# Sedna_Monitor_Board.net
KiCad netlist of a schematic drawn in EAGLE
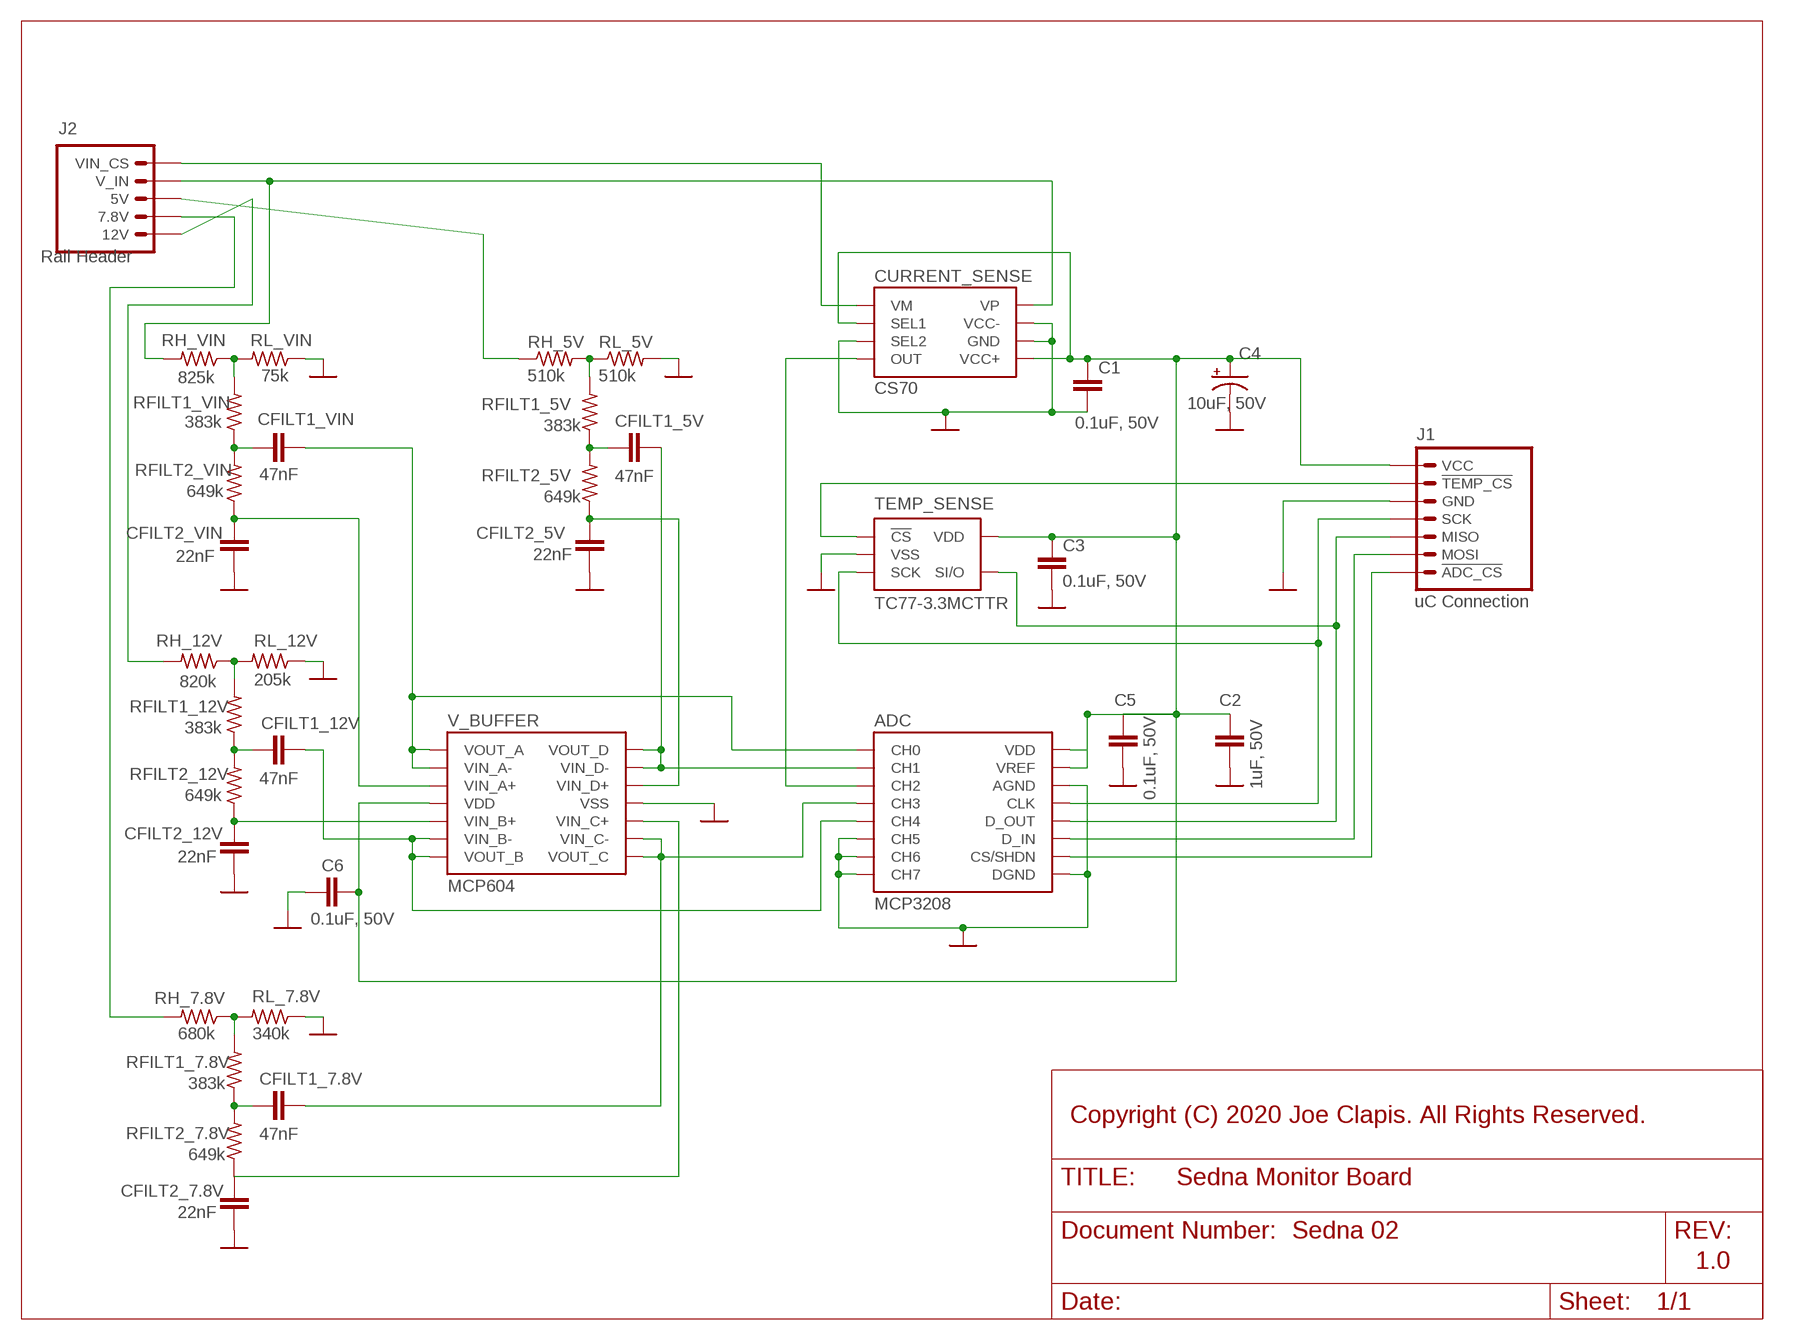
[diagram p0: schematic, sheet 1]

(export (version "E")
  (design (tool "Eeschema 10.0.6"))
  (components
    (comp (ref "ADC")
      (value "MCP3208")
      (footprint "eagle-import:MICROCHIP_SOIC-16_SL")
      (libsource (lib "eagle-import") (part "MCP3208"))
    )
    (comp (ref "C1")
      (value "0.1uF, 50V")
      (footprint "eagle-import:C0805")
      (libsource (lib "eagle-import") (part "C-EUC0805"))
    )
    (comp (ref "C2")
      (value "1uF, 50V")
      (footprint "eagle-import:C0805")
      (libsource (lib "eagle-import") (part "C-EUC0805"))
    )
    (comp (ref "C3")
      (value "0.1uF, 50V")
      (footprint "eagle-import:C0805")
      (libsource (lib "eagle-import") (part "C-EUC0805"))
    )
    (comp (ref "C4")
      (value "10uF, 50V")
      (footprint "eagle-import:PANASONIC-SMD-CAP-SV-D")
      (libsource (lib "eagle-import") (part "PANASONIC-CAP-SV"))
    )
    (comp (ref "C5")
      (value "0.1uF, 50V")
      (footprint "eagle-import:C0805")
      (libsource (lib "eagle-import") (part "C-EUC0805"))
    )
    (comp (ref "C6")
      (value "0.1uF, 50V")
      (footprint "eagle-import:C0805")
      (libsource (lib "eagle-import") (part "C-EUC0805"))
    )
    (comp (ref "CFILT1_5V")
      (value "47nF")
      (footprint "eagle-import:C0805")
      (libsource (lib "eagle-import") (part "C-EUC0805"))
    )
    (comp (ref "CFILT1_7.8V")
      (value "47nF")
      (footprint "eagle-import:C0805")
      (libsource (lib "eagle-import") (part "C-EUC0805"))
    )
    (comp (ref "CFILT1_12V")
      (value "47nF")
      (footprint "eagle-import:C0805")
      (libsource (lib "eagle-import") (part "C-EUC0805"))
    )
    (comp (ref "CFILT1_VIN")
      (value "47nF")
      (footprint "eagle-import:C0805")
      (libsource (lib "eagle-import") (part "C-EUC0805"))
    )
    (comp (ref "CFILT2_5V")
      (value "22nF")
      (footprint "eagle-import:C0805")
      (libsource (lib "eagle-import") (part "C-EUC0805"))
    )
    (comp (ref "CFILT2_7.8V")
      (value "22nF")
      (footprint "eagle-import:C0805")
      (libsource (lib "eagle-import") (part "C-EUC0805"))
    )
    (comp (ref "CFILT2_12V")
      (value "22nF")
      (footprint "eagle-import:C0805")
      (libsource (lib "eagle-import") (part "C-EUC0805"))
    )
    (comp (ref "CFILT2_VIN")
      (value "22nF")
      (footprint "eagle-import:C0805")
      (libsource (lib "eagle-import") (part "C-EUC0805"))
    )
    (comp (ref "CURRENT_SENSE")
      (value "CS70")
      (footprint "eagle-import:TSSOP8")
      (libsource (lib "eagle-import") (part "CS70"))
    )
    (comp (ref "J1")
      (value "uC Connection")
      (footprint "eagle-import:1X07")
      (libsource (lib "eagle-import") (part "UC_MONITOR_HEADER"))
    )
    (comp (ref "J2")
      (value "Rail Header")
      (footprint "eagle-import:1X05")
      (libsource (lib "eagle-import") (part "RAIL_HEADER"))
    )
    (comp (ref "RFILT1_5V")
      (value "383k")
      (footprint "eagle-import:R0805")
      (libsource (lib "eagle-import") (part "R-US_R0805"))
    )
    (comp (ref "RFILT1_7.8V")
      (value "383k")
      (footprint "eagle-import:R0805")
      (libsource (lib "eagle-import") (part "R-US_R0805"))
    )
    (comp (ref "RFILT1_12V")
      (value "383k")
      (footprint "eagle-import:R0805")
      (libsource (lib "eagle-import") (part "R-US_R0805"))
    )
    (comp (ref "RFILT1_VIN")
      (value "383k")
      (footprint "eagle-import:R0805")
      (libsource (lib "eagle-import") (part "R-US_R0805"))
    )
    (comp (ref "RFILT2_5V")
      (value "649k")
      (footprint "eagle-import:R0805")
      (libsource (lib "eagle-import") (part "R-US_R0805"))
    )
    (comp (ref "RFILT2_7.8V")
      (value "649k")
      (footprint "eagle-import:R0805")
      (libsource (lib "eagle-import") (part "R-US_R0805"))
    )
    (comp (ref "RFILT2_12V")
      (value "649k")
      (footprint "eagle-import:R0805")
      (libsource (lib "eagle-import") (part "R-US_R0805"))
    )
    (comp (ref "RFILT2_VIN")
      (value "649k")
      (footprint "eagle-import:R0805")
      (libsource (lib "eagle-import") (part "R-US_R0805"))
    )
    (comp (ref "RH_5V")
      (value "510k")
      (footprint "eagle-import:R0805")
      (libsource (lib "eagle-import") (part "R-US_R0805"))
    )
    (comp (ref "RH_7.8V")
      (value "680k")
      (footprint "eagle-import:R0805")
      (libsource (lib "eagle-import") (part "R-US_R0805"))
    )
    (comp (ref "RH_12V")
      (value "820k")
      (footprint "eagle-import:R0805")
      (libsource (lib "eagle-import") (part "R-US_R0805"))
    )
    (comp (ref "RH_VIN")
      (value "825k")
      (footprint "eagle-import:R0805")
      (libsource (lib "eagle-import") (part "R-US_R0805"))
    )
    (comp (ref "RL_5V")
      (value "510k")
      (footprint "eagle-import:R0805")
      (libsource (lib "eagle-import") (part "R-US_R0805"))
    )
    (comp (ref "RL_7.8V")
      (value "340k")
      (footprint "eagle-import:R0805")
      (libsource (lib "eagle-import") (part "R-US_R0805"))
    )
    (comp (ref "RL_12V")
      (value "205k")
      (footprint "eagle-import:R0805")
      (libsource (lib "eagle-import") (part "R-US_R0805"))
    )
    (comp (ref "RL_VIN")
      (value "75k")
      (footprint "eagle-import:R0805")
      (libsource (lib "eagle-import") (part "R-US_R0805"))
    )
    (comp (ref "TEMP_SENSE")
      (value "TC77-3.3MCTTR")
      (footprint "eagle-import:MICROCHIP_SOT-23_5_OT")
      (libsource (lib "eagle-import") (part "TC77MCT"))
    )
    (comp (ref "V_BUFFER")
      (value "MCP604")
      (footprint "eagle-import:MICROCHIP_TSSOP-14_ST")
      (libsource (lib "eagle-import") (part "MCP604ST"))
    )
  )
  (nets
    (net (code "1") (name "GND") (class "Default")
      (node (ref "ADC") (pin "14") (pinfunction "AGND_14") (pintype "power_in"))
      (node (ref "ADC") (pin "6") (pinfunction "CH5_6") (pintype "input"))
      (node (ref "ADC") (pin "7") (pinfunction "CH6_7") (pintype "input"))
      (node (ref "ADC") (pin "8") (pinfunction "CH7_8") (pintype "input"))
      (node (ref "ADC") (pin "9") (pinfunction "DGND_9") (pintype "power_in"))
      (node (ref "C1") (pin "2") (pinfunction "2_2") (pintype "passive"))
      (node (ref "C2") (pin "2") (pinfunction "2_2") (pintype "passive"))
      (node (ref "C3") (pin "2") (pinfunction "2_2") (pintype "passive"))
      (node (ref "C4") (pin "GND") (pinfunction "-_GND") (pintype "passive"))
      (node (ref "C5") (pin "2") (pinfunction "2_2") (pintype "passive"))
      (node (ref "C6") (pin "2") (pinfunction "2_2") (pintype "passive"))
      (node (ref "CFILT2_12V") (pin "1") (pinfunction "1_1") (pintype "passive"))
      (node (ref "CFILT2_5V") (pin "1") (pinfunction "1_1") (pintype "passive"))
      (node (ref "CFILT2_7.8V") (pin "1") (pinfunction "1_1") (pintype "passive"))
      (node (ref "CFILT2_VIN") (pin "1") (pinfunction "1_1") (pintype "passive"))
      (node (ref "CURRENT_SENSE") (pin "3") (pinfunction "SEL2_3") (pintype "input"))
      (node (ref "CURRENT_SENSE") (pin "6") (pinfunction "GND_6") (pintype "power_in"))
      (node (ref "CURRENT_SENSE") (pin "7") (pinfunction "VCC-_7") (pintype "power_in"))
      (node (ref "J1") (pin "3") (pinfunction "GND_3") (pintype "output"))
      (node (ref "RL_12V") (pin "1") (pinfunction "1_1") (pintype "passive"))
      (node (ref "RL_5V") (pin "2") (pinfunction "2_2") (pintype "passive"))
      (node (ref "RL_7.8V") (pin "1") (pinfunction "1_1") (pintype "passive"))
      (node (ref "RL_VIN") (pin "1") (pinfunction "1_1") (pintype "passive"))
      (node (ref "TEMP_SENSE") (pin "2") (pinfunction "VSS_2") (pintype "power_in"))
      (node (ref "V_BUFFER") (pin "11") (pinfunction "VSS_11") (pintype "power_in"))
    )
    (net (code "2") (name "Net-(ADC-CH0)") (class "Default")
      (node (ref "ADC") (pin "1") (pinfunction "CH0_1") (pintype "input"))
      (node (ref "CFILT1_VIN") (pin "2") (pinfunction "2_2") (pintype "passive"))
      (node (ref "V_BUFFER") (pin "1") (pinfunction "VOUT_A_1") (pintype "output"))
      (node (ref "V_BUFFER") (pin "2") (pinfunction "VIN_A-_2") (pintype "input"))
    )
    (net (code "3") (name "Net-(ADC-CH1)") (class "Default")
      (node (ref "ADC") (pin "2") (pinfunction "CH1_2") (pintype "input"))
      (node (ref "CFILT1_5V") (pin "1") (pinfunction "1_1") (pintype "passive"))
      (node (ref "V_BUFFER") (pin "13") (pinfunction "VIN_D-_13") (pintype "input"))
      (node (ref "V_BUFFER") (pin "14") (pinfunction "VOUT_D_14") (pintype "output"))
    )
    (net (code "4") (name "Net-(ADC-CH2)") (class "Default")
      (node (ref "ADC") (pin "3") (pinfunction "CH2_3") (pintype "input"))
      (node (ref "CURRENT_SENSE") (pin "4") (pinfunction "OUT_4") (pintype "output"))
    )
    (net (code "5") (name "Net-(ADC-CH3)") (class "Default")
      (node (ref "ADC") (pin "4") (pinfunction "CH3_4") (pintype "input"))
      (node (ref "CFILT1_7.8V") (pin "1") (pinfunction "1_1") (pintype "passive"))
      (node (ref "V_BUFFER") (pin "8") (pinfunction "VOUT_C_8") (pintype "output"))
      (node (ref "V_BUFFER") (pin "9") (pinfunction "VIN_C-_9") (pintype "input"))
    )
    (net (code "6") (name "Net-(ADC-CH4)") (class "Default")
      (node (ref "ADC") (pin "5") (pinfunction "CH4_5") (pintype "input"))
      (node (ref "CFILT1_12V") (pin "2") (pinfunction "2_2") (pintype "passive"))
      (node (ref "V_BUFFER") (pin "6") (pinfunction "VIN_B-_6") (pintype "input"))
      (node (ref "V_BUFFER") (pin "7") (pinfunction "VOUT_B_7") (pintype "output"))
    )
    (net (code "7") (name "Net-(ADC-CLK)") (class "Default")
      (node (ref "ADC") (pin "13") (pinfunction "CLK_13") (pintype "input"))
      (node (ref "J1") (pin "4") (pinfunction "SCK_4") (pintype "output"))
      (node (ref "TEMP_SENSE") (pin "3") (pinfunction "SCK_3") (pintype "input"))
    )
    (net (code "8") (name "Net-(ADC-CS{slash}SHDN)") (class "Default")
      (node (ref "ADC") (pin "10") (pinfunction "CS/SHDN_10") (pintype "input"))
      (node (ref "J1") (pin "7") (pinfunction "~{ADC_CS}_7") (pintype "power_in"))
    )
    (net (code "9") (name "Net-(ADC-D_IN)") (class "Default")
      (node (ref "ADC") (pin "11") (pinfunction "D_IN_11") (pintype "input"))
      (node (ref "J1") (pin "6") (pinfunction "MOSI_6") (pintype "output"))
    )
    (net (code "10") (name "Net-(ADC-D_OUT)") (class "Default")
      (node (ref "ADC") (pin "12") (pinfunction "D_OUT_12") (pintype "output"))
      (node (ref "J1") (pin "5") (pinfunction "MISO_5") (pintype "input"))
      (node (ref "TEMP_SENSE") (pin "4") (pinfunction "SI/O_4") (pintype "output"))
    )
    (net (code "11") (name "Net-(ADC-VDD)") (class "Default")
      (node (ref "ADC") (pin "15") (pinfunction "VREF_15") (pintype "input"))
      (node (ref "ADC") (pin "16") (pinfunction "VDD_16") (pintype "power_in"))
      (node (ref "C1") (pin "1") (pinfunction "1_1") (pintype "passive"))
      (node (ref "C2") (pin "1") (pinfunction "1_1") (pintype "passive"))
      (node (ref "C3") (pin "1") (pinfunction "1_1") (pintype "passive"))
      (node (ref "C4") (pin "VDD") (pinfunction "+_VDD") (pintype "passive"))
      (node (ref "C5") (pin "1") (pinfunction "1_1") (pintype "passive"))
      (node (ref "C6") (pin "1") (pinfunction "1_1") (pintype "passive"))
      (node (ref "CURRENT_SENSE") (pin "2") (pinfunction "SEL1_2") (pintype "input"))
      (node (ref "CURRENT_SENSE") (pin "5") (pinfunction "VCC+_5") (pintype "power_in"))
      (node (ref "J1") (pin "1") (pinfunction "VCC_1") (pintype "power_in"))
      (node (ref "TEMP_SENSE") (pin "5") (pinfunction "VDD_5") (pintype "power_in"))
      (node (ref "V_BUFFER") (pin "4") (pinfunction "VDD_4") (pintype "power_in"))
    )
    (net (code "12") (name "Net-(CFILT1_5V-Pad2)") (class "Default")
      (node (ref "CFILT1_5V") (pin "2") (pinfunction "2_2") (pintype "passive"))
      (node (ref "RFILT1_5V") (pin "1") (pinfunction "1_1") (pintype "passive"))
      (node (ref "RFILT2_5V") (pin "2") (pinfunction "2_2") (pintype "passive"))
    )
    (net (code "13") (name "Net-(CFILT1_7.8V-Pad2)") (class "Default")
      (node (ref "CFILT1_7.8V") (pin "2") (pinfunction "2_2") (pintype "passive"))
      (node (ref "RFILT1_7.8V") (pin "1") (pinfunction "1_1") (pintype "passive"))
      (node (ref "RFILT2_7.8V") (pin "2") (pinfunction "2_2") (pintype "passive"))
    )
    (net (code "14") (name "Net-(CFILT1_12V-Pad1)") (class "Default")
      (node (ref "CFILT1_12V") (pin "1") (pinfunction "1_1") (pintype "passive"))
      (node (ref "RFILT1_12V") (pin "1") (pinfunction "1_1") (pintype "passive"))
      (node (ref "RFILT2_12V") (pin "2") (pinfunction "2_2") (pintype "passive"))
    )
    (net (code "15") (name "Net-(CFILT1_VIN-Pad1)") (class "Default")
      (node (ref "CFILT1_VIN") (pin "1") (pinfunction "1_1") (pintype "passive"))
      (node (ref "RFILT1_VIN") (pin "1") (pinfunction "1_1") (pintype "passive"))
      (node (ref "RFILT2_VIN") (pin "2") (pinfunction "2_2") (pintype "passive"))
    )
    (net (code "16") (name "Net-(CURRENT_SENSE-VM)") (class "Default")
      (node (ref "CURRENT_SENSE") (pin "1") (pinfunction "VM_1") (pintype "input"))
      (node (ref "J2") (pin "1") (pinfunction "VIN_CS_1") (pintype "output"))
    )
    (net (code "17") (name "Net-(CURRENT_SENSE-VP)") (class "Default")
      (node (ref "CURRENT_SENSE") (pin "8") (pinfunction "VP_8") (pintype "input"))
      (node (ref "J2") (pin "2") (pinfunction "V_IN_2") (pintype "output"))
      (node (ref "RH_VIN") (pin "2") (pinfunction "2_2") (pintype "passive"))
    )
    (net (code "18") (name "Net-(J1-~{TEMP_CS})") (class "Default")
      (node (ref "J1") (pin "2") (pinfunction "~{TEMP_CS}_2") (pintype "output"))
      (node (ref "TEMP_SENSE") (pin "1") (pinfunction "~{CS}_1") (pintype "input"))
    )
    (net (code "19") (name "Net-(J2-5V)") (class "Default")
      (node (ref "J2") (pin "3") (pinfunction "5V_3") (pintype "output"))
      (node (ref "RH_5V") (pin "1") (pinfunction "1_1") (pintype "passive"))
    )
    (net (code "20") (name "Net-(J2-7.8V)") (class "Default")
      (node (ref "J2") (pin "4") (pinfunction "7.8V_4") (pintype "output"))
      (node (ref "RH_7.8V") (pin "2") (pinfunction "2_2") (pintype "passive"))
    )
    (net (code "21") (name "Net-(J2-12V)") (class "Default")
      (node (ref "J2") (pin "5") (pinfunction "12V_5") (pintype "output"))
      (node (ref "RH_12V") (pin "2") (pinfunction "2_2") (pintype "passive"))
    )
    (net (code "22") (name "Net-(RFILT1_5V-Pad2)") (class "Default")
      (node (ref "RFILT1_5V") (pin "2") (pinfunction "2_2") (pintype "passive"))
      (node (ref "RH_5V") (pin "2") (pinfunction "2_2") (pintype "passive"))
      (node (ref "RL_5V") (pin "1") (pinfunction "1_1") (pintype "passive"))
    )
    (net (code "23") (name "Net-(RFILT1_7.8V-Pad2)") (class "Default")
      (node (ref "RFILT1_7.8V") (pin "2") (pinfunction "2_2") (pintype "passive"))
      (node (ref "RH_7.8V") (pin "1") (pinfunction "1_1") (pintype "passive"))
      (node (ref "RL_7.8V") (pin "2") (pinfunction "2_2") (pintype "passive"))
    )
    (net (code "24") (name "Net-(RFILT1_12V-Pad2)") (class "Default")
      (node (ref "RFILT1_12V") (pin "2") (pinfunction "2_2") (pintype "passive"))
      (node (ref "RH_12V") (pin "1") (pinfunction "1_1") (pintype "passive"))
      (node (ref "RL_12V") (pin "2") (pinfunction "2_2") (pintype "passive"))
    )
    (net (code "25") (name "Net-(RFILT1_VIN-Pad2)") (class "Default")
      (node (ref "RFILT1_VIN") (pin "2") (pinfunction "2_2") (pintype "passive"))
      (node (ref "RH_VIN") (pin "1") (pinfunction "1_1") (pintype "passive"))
      (node (ref "RL_VIN") (pin "2") (pinfunction "2_2") (pintype "passive"))
    )
    (net (code "26") (name "Net-(V_BUFFER-VIN_A+)") (class "Default")
      (node (ref "CFILT2_VIN") (pin "2") (pinfunction "2_2") (pintype "passive"))
      (node (ref "RFILT2_VIN") (pin "1") (pinfunction "1_1") (pintype "passive"))
      (node (ref "V_BUFFER") (pin "3") (pinfunction "VIN_A+_3") (pintype "input"))
    )
    (net (code "27") (name "Net-(V_BUFFER-VIN_B+)") (class "Default")
      (node (ref "CFILT2_12V") (pin "2") (pinfunction "2_2") (pintype "passive"))
      (node (ref "RFILT2_12V") (pin "1") (pinfunction "1_1") (pintype "passive"))
      (node (ref "V_BUFFER") (pin "5") (pinfunction "VIN_B+_5") (pintype "input"))
    )
    (net (code "28") (name "Net-(V_BUFFER-VIN_C+)") (class "Default")
      (node (ref "CFILT2_7.8V") (pin "2") (pinfunction "2_2") (pintype "passive"))
      (node (ref "RFILT2_7.8V") (pin "1") (pinfunction "1_1") (pintype "passive"))
      (node (ref "V_BUFFER") (pin "10") (pinfunction "VIN_C+_10") (pintype "input"))
    )
    (net (code "29") (name "Net-(V_BUFFER-VIN_D+)") (class "Default")
      (node (ref "CFILT2_5V") (pin "2") (pinfunction "2_2") (pintype "passive"))
      (node (ref "RFILT2_5V") (pin "1") (pinfunction "1_1") (pintype "passive"))
      (node (ref "V_BUFFER") (pin "12") (pinfunction "VIN_D+_12") (pintype "input"))
    )
  )
)
